# SCH_HallVoltageLV25np.net
KiCad netlist of a schematic drawn in Altium Designer
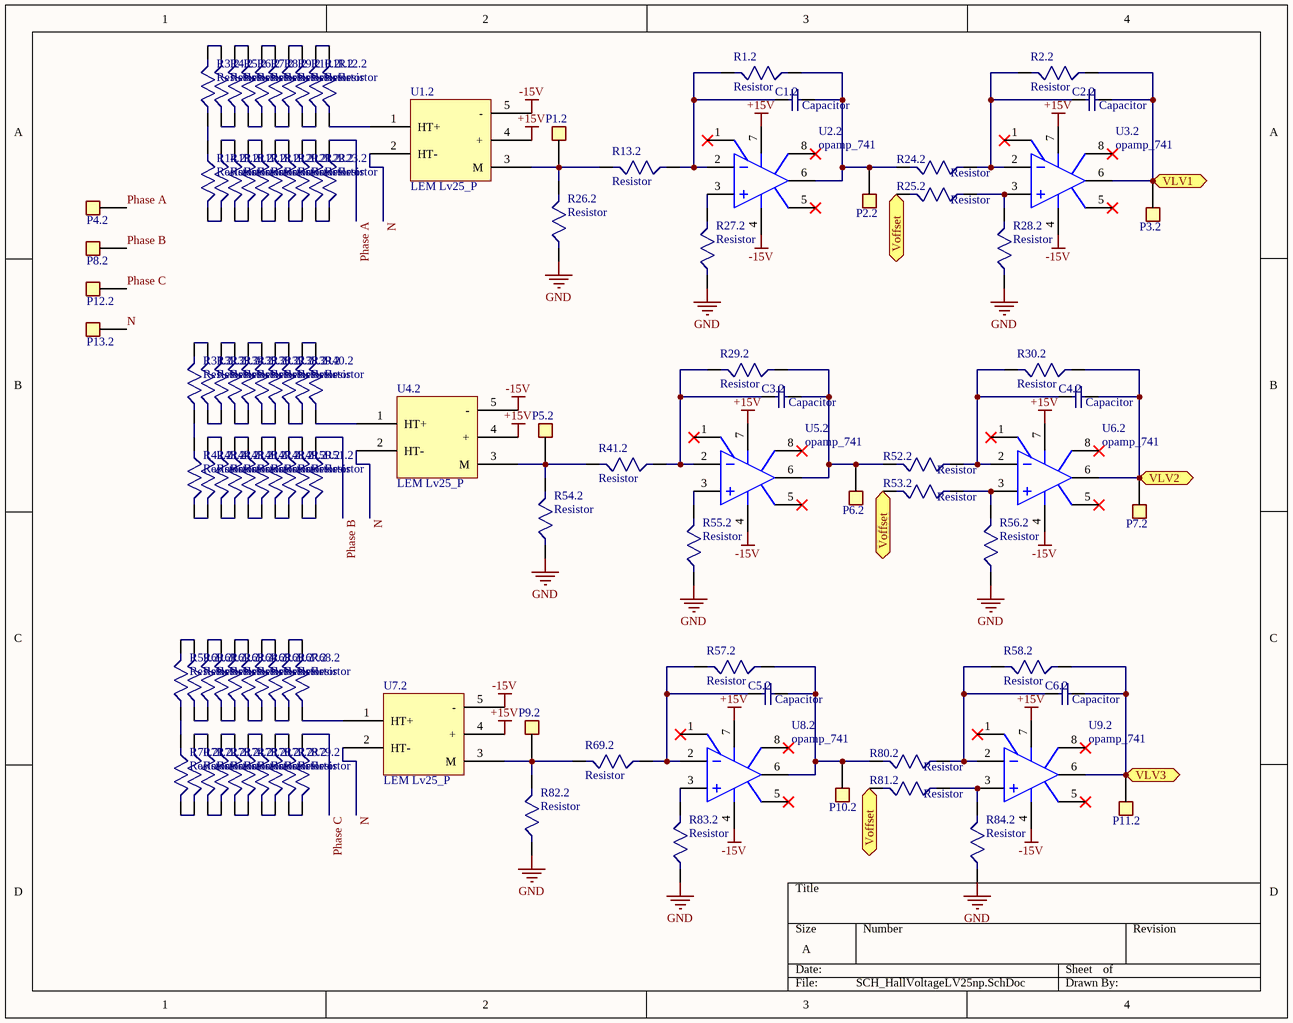
[diagram p0: SCH_HallVoltageLV25np.SchDoc]

(export (version "E")
  (design (tool "Eeschema 10.0.6"))
  (components
    (comp (ref "C1.2")
      (value "Capacitor")
      (footprint "CAPC0805")
      (description "capacitor non polar")
      (libsource (lib "thuvien_altium") (part "capacitor_non_polar"))
    )
    (comp (ref "C2.2")
      (value "Capacitor")
      (footprint "CAPC0805")
      (description "capacitor non polar")
      (libsource (lib "thuvien_altium") (part "capacitor_non_polar"))
    )
    (comp (ref "C3.2")
      (value "Capacitor")
      (footprint "CAPC0805")
      (description "capacitor non polar")
      (libsource (lib "thuvien_altium") (part "capacitor_non_polar"))
    )
    (comp (ref "C4.2")
      (value "Capacitor")
      (footprint "CAPC0805")
      (description "capacitor non polar")
      (libsource (lib "thuvien_altium") (part "capacitor_non_polar"))
    )
    (comp (ref "C5.2")
      (value "Capacitor")
      (footprint "CAPC0805")
      (description "capacitor non polar")
      (libsource (lib "thuvien_altium") (part "capacitor_non_polar"))
    )
    (comp (ref "C6.2")
      (value "Capacitor")
      (footprint "CAPC0805")
      (description "capacitor non polar")
      (libsource (lib "thuvien_altium") (part "capacitor_non_polar"))
    )
    (comp (ref "P1.2")
      (value "testpin")
      (footprint "thuvien_altium:tp_red_1p")
      (libsource (lib "") (part "testpin_1"))
    )
    (comp (ref "P2.2")
      (value "testpin")
      (footprint "thuvien_altium:tp_red_1p")
      (libsource (lib "thuvien_altium") (part "testpin"))
    )
    (comp (ref "P3.2")
      (value "testpin")
      (footprint "thuvien_altium:tp_red_1p")
      (libsource (lib "thuvien_altium") (part "testpin"))
    )
    (comp (ref "P4.2")
      (value "Terminal on PCB")
      (footprint "thuvien_altium:Terminal M5")
      (libsource (lib "thuvien_altium") (part "Terminal on PCB"))
    )
    (comp (ref "P5.2")
      (value "testpin")
      (footprint "thuvien_altium:tp_red_1p")
      (libsource (lib "") (part "testpin_1"))
    )
    (comp (ref "P6.2")
      (value "testpin")
      (footprint "thuvien_altium:tp_red_1p")
      (libsource (lib "thuvien_altium") (part "testpin"))
    )
    (comp (ref "P7.2")
      (value "testpin")
      (footprint "thuvien_altium:tp_red_1p")
      (libsource (lib "thuvien_altium") (part "testpin"))
    )
    (comp (ref "P8.2")
      (value "Terminal on PCB")
      (footprint "thuvien_altium:Terminal M5")
      (libsource (lib "thuvien_altium") (part "Terminal on PCB"))
    )
    (comp (ref "P9.2")
      (value "testpin")
      (footprint "thuvien_altium:tp_red_1p")
      (libsource (lib "") (part "testpin_1"))
    )
    (comp (ref "P10.2")
      (value "testpin")
      (footprint "thuvien_altium:tp_red_1p")
      (libsource (lib "thuvien_altium") (part "testpin"))
    )
    (comp (ref "P11.2")
      (value "testpin")
      (footprint "thuvien_altium:tp_red_1p")
      (libsource (lib "thuvien_altium") (part "testpin"))
    )
    (comp (ref "P12.2")
      (value "Terminal on PCB")
      (footprint "thuvien_altium:Terminal M5")
      (libsource (lib "thuvien_altium") (part "Terminal on PCB"))
    )
    (comp (ref "P13.2")
      (value "Terminal on PCB")
      (footprint "thuvien_altium:Terminal M5")
      (libsource (lib "thuvien_altium") (part "Terminal on PCB"))
    )
    (comp (ref "R1.2")
      (value "Resistor")
      (footprint "RESC0805")
      (description "resistor")
      (libsource (lib "thuvien_altium") (part "resistor"))
    )
    (comp (ref "R2.2")
      (value "Resistor")
      (footprint "RESC0805")
      (description "resistor")
      (libsource (lib "thuvien_altium") (part "resistor"))
    )
    (comp (ref "R3.2")
      (value "Resistor")
      (footprint "RESC0805")
      (description "resistor")
      (libsource (lib "thuvien_altium") (part "resistor"))
    )
    (comp (ref "R4.2")
      (value "Resistor")
      (footprint "RESC0805")
      (description "resistor")
      (libsource (lib "thuvien_altium") (part "resistor"))
    )
    (comp (ref "R5.2")
      (value "Resistor")
      (footprint "RESC0805")
      (description "resistor")
      (libsource (lib "thuvien_altium") (part "resistor"))
    )
    (comp (ref "R6.2")
      (value "Resistor")
      (footprint "RESC0805")
      (description "resistor")
      (libsource (lib "thuvien_altium") (part "resistor"))
    )
    (comp (ref "R7.2")
      (value "Resistor")
      (footprint "RESC0805")
      (description "resistor")
      (libsource (lib "thuvien_altium") (part "resistor"))
    )
    (comp (ref "R8.2")
      (value "Resistor")
      (footprint "RESC0805")
      (description "resistor")
      (libsource (lib "thuvien_altium") (part "resistor"))
    )
    (comp (ref "R9.2")
      (value "Resistor")
      (footprint "RESC0805")
      (description "resistor")
      (libsource (lib "thuvien_altium") (part "resistor"))
    )
    (comp (ref "R10.2")
      (value "Resistor")
      (footprint "RESC0805")
      (description "resistor")
      (libsource (lib "thuvien_altium") (part "resistor"))
    )
    (comp (ref "R11.2")
      (value "Resistor")
      (footprint "RESC0805")
      (description "resistor")
      (libsource (lib "thuvien_altium") (part "resistor"))
    )
    (comp (ref "R12.2")
      (value "Resistor")
      (footprint "RESC0805")
      (description "resistor")
      (libsource (lib "thuvien_altium") (part "resistor"))
    )
    (comp (ref "R13.2")
      (value "Resistor")
      (footprint "RESC0805")
      (description "resistor")
      (libsource (lib "thuvien_altium") (part "resistor"))
    )
    (comp (ref "R14.2")
      (value "Resistor")
      (footprint "RESC0805")
      (description "resistor")
      (libsource (lib "thuvien_altium") (part "resistor"))
    )
    (comp (ref "R15.2")
      (value "Resistor")
      (footprint "RESC0805")
      (description "resistor")
      (libsource (lib "thuvien_altium") (part "resistor"))
    )
    (comp (ref "R16.2")
      (value "Resistor")
      (footprint "RESC0805")
      (description "resistor")
      (libsource (lib "thuvien_altium") (part "resistor"))
    )
    (comp (ref "R17.2")
      (value "Resistor")
      (footprint "RESC0805")
      (description "resistor")
      (libsource (lib "thuvien_altium") (part "resistor"))
    )
    (comp (ref "R18.2")
      (value "Resistor")
      (footprint "RESC0805")
      (description "resistor")
      (libsource (lib "thuvien_altium") (part "resistor"))
    )
    (comp (ref "R19.2")
      (value "Resistor")
      (footprint "RESC0805")
      (description "resistor")
      (libsource (lib "thuvien_altium") (part "resistor"))
    )
    (comp (ref "R20.2")
      (value "Resistor")
      (footprint "RESC0805")
      (description "resistor")
      (libsource (lib "thuvien_altium") (part "resistor"))
    )
    (comp (ref "R21.2")
      (value "Resistor")
      (footprint "RESC0805")
      (description "resistor")
      (libsource (lib "thuvien_altium") (part "resistor"))
    )
    (comp (ref "R22.2")
      (value "Resistor")
      (footprint "RESC0805")
      (description "resistor")
      (libsource (lib "thuvien_altium") (part "resistor"))
    )
    (comp (ref "R23.2")
      (value "Resistor")
      (footprint "RESC0805")
      (description "resistor")
      (libsource (lib "thuvien_altium") (part "resistor"))
    )
    (comp (ref "R24.2")
      (value "Resistor")
      (footprint "RESC0805")
      (description "resistor")
      (libsource (lib "thuvien_altium") (part "resistor"))
    )
    (comp (ref "R25.2")
      (value "Resistor")
      (footprint "RESC0805")
      (description "resistor")
      (libsource (lib "thuvien_altium") (part "resistor"))
    )
    (comp (ref "R26.2")
      (value "Resistor")
      (footprint "RESC0805")
      (description "resistor")
      (libsource (lib "thuvien_altium") (part "resistor"))
    )
    (comp (ref "R27.2")
      (value "Resistor")
      (footprint "RESC0805")
      (description "resistor")
      (libsource (lib "thuvien_altium") (part "resistor"))
    )
    (comp (ref "R28.2")
      (value "Resistor")
      (footprint "RESC0805")
      (description "resistor")
      (libsource (lib "thuvien_altium") (part "resistor"))
    )
    (comp (ref "R29.2")
      (value "Resistor")
      (footprint "RESC0805")
      (description "resistor")
      (libsource (lib "thuvien_altium") (part "resistor"))
    )
    (comp (ref "R30.2")
      (value "Resistor")
      (footprint "RESC0805")
      (description "resistor")
      (libsource (lib "thuvien_altium") (part "resistor"))
    )
    (comp (ref "R31.2")
      (value "Resistor")
      (footprint "RESC0805")
      (description "resistor")
      (libsource (lib "thuvien_altium") (part "resistor"))
    )
    (comp (ref "R32.2")
      (value "Resistor")
      (footprint "RESC0805")
      (description "resistor")
      (libsource (lib "thuvien_altium") (part "resistor"))
    )
    (comp (ref "R33.2")
      (value "Resistor")
      (footprint "RESC0805")
      (description "resistor")
      (libsource (lib "thuvien_altium") (part "resistor"))
    )
    (comp (ref "R34.2")
      (value "Resistor")
      (footprint "RESC0805")
      (description "resistor")
      (libsource (lib "thuvien_altium") (part "resistor"))
    )
    (comp (ref "R35.2")
      (value "Resistor")
      (footprint "RESC0805")
      (description "resistor")
      (libsource (lib "thuvien_altium") (part "resistor"))
    )
    (comp (ref "R36.2")
      (value "Resistor")
      (footprint "RESC0805")
      (description "resistor")
      (libsource (lib "thuvien_altium") (part "resistor"))
    )
    (comp (ref "R37.2")
      (value "Resistor")
      (footprint "RESC0805")
      (description "resistor")
      (libsource (lib "thuvien_altium") (part "resistor"))
    )
    (comp (ref "R38.2")
      (value "Resistor")
      (footprint "RESC0805")
      (description "resistor")
      (libsource (lib "thuvien_altium") (part "resistor"))
    )
    (comp (ref "R39.2")
      (value "Resistor")
      (footprint "RESC0805")
      (description "resistor")
      (libsource (lib "thuvien_altium") (part "resistor"))
    )
    (comp (ref "R40.2")
      (value "Resistor")
      (footprint "RESC0805")
      (description "resistor")
      (libsource (lib "thuvien_altium") (part "resistor"))
    )
    (comp (ref "R41.2")
      (value "Resistor")
      (footprint "RESC0805")
      (description "resistor")
      (libsource (lib "thuvien_altium") (part "resistor"))
    )
    (comp (ref "R42.2")
      (value "Resistor")
      (footprint "RESC0805")
      (description "resistor")
      (libsource (lib "thuvien_altium") (part "resistor"))
    )
    (comp (ref "R43.2")
      (value "Resistor")
      (footprint "RESC0805")
      (description "resistor")
      (libsource (lib "thuvien_altium") (part "resistor"))
    )
    (comp (ref "R44.2")
      (value "Resistor")
      (footprint "RESC0805")
      (description "resistor")
      (libsource (lib "thuvien_altium") (part "resistor"))
    )
    (comp (ref "R45.2")
      (value "Resistor")
      (footprint "RESC0805")
      (description "resistor")
      (libsource (lib "thuvien_altium") (part "resistor"))
    )
    (comp (ref "R46.2")
      (value "Resistor")
      (footprint "RESC0805")
      (description "resistor")
      (libsource (lib "thuvien_altium") (part "resistor"))
    )
    (comp (ref "R47.2")
      (value "Resistor")
      (footprint "RESC0805")
      (description "resistor")
      (libsource (lib "thuvien_altium") (part "resistor"))
    )
    (comp (ref "R48.2")
      (value "Resistor")
      (footprint "RESC0805")
      (description "resistor")
      (libsource (lib "thuvien_altium") (part "resistor"))
    )
    (comp (ref "R49.2")
      (value "Resistor")
      (footprint "RESC0805")
      (description "resistor")
      (libsource (lib "thuvien_altium") (part "resistor"))
    )
    (comp (ref "R50.2")
      (value "Resistor")
      (footprint "RESC0805")
      (description "resistor")
      (libsource (lib "thuvien_altium") (part "resistor"))
    )
    (comp (ref "R51.2")
      (value "Resistor")
      (footprint "RESC0805")
      (description "resistor")
      (libsource (lib "thuvien_altium") (part "resistor"))
    )
    (comp (ref "R52.2")
      (value "Resistor")
      (footprint "RESC0805")
      (description "resistor")
      (libsource (lib "thuvien_altium") (part "resistor"))
    )
    (comp (ref "R53.2")
      (value "Resistor")
      (footprint "RESC0805")
      (description "resistor")
      (libsource (lib "thuvien_altium") (part "resistor"))
    )
    (comp (ref "R54.2")
      (value "Resistor")
      (footprint "RESC0805")
      (description "resistor")
      (libsource (lib "thuvien_altium") (part "resistor"))
    )
    (comp (ref "R55.2")
      (value "Resistor")
      (footprint "RESC0805")
      (description "resistor")
      (libsource (lib "thuvien_altium") (part "resistor"))
    )
    (comp (ref "R56.2")
      (value "Resistor")
      (footprint "RESC0805")
      (description "resistor")
      (libsource (lib "thuvien_altium") (part "resistor"))
    )
    (comp (ref "R57.2")
      (value "Resistor")
      (footprint "RESC0805")
      (description "resistor")
      (libsource (lib "thuvien_altium") (part "resistor"))
    )
    (comp (ref "R58.2")
      (value "Resistor")
      (footprint "RESC0805")
      (description "resistor")
      (libsource (lib "thuvien_altium") (part "resistor"))
    )
    (comp (ref "R59.2")
      (value "Resistor")
      (footprint "RESC0805")
      (description "resistor")
      (libsource (lib "thuvien_altium") (part "resistor"))
    )
    (comp (ref "R60.2")
      (value "Resistor")
      (footprint "RESC0805")
      (description "resistor")
      (libsource (lib "thuvien_altium") (part "resistor"))
    )
    (comp (ref "R61.2")
      (value "Resistor")
      (footprint "RESC0805")
      (description "resistor")
      (libsource (lib "thuvien_altium") (part "resistor"))
    )
    (comp (ref "R62.2")
      (value "Resistor")
      (footprint "RESC0805")
      (description "resistor")
      (libsource (lib "thuvien_altium") (part "resistor"))
    )
    (comp (ref "R63.2")
      (value "Resistor")
      (footprint "RESC0805")
      (description "resistor")
      (libsource (lib "thuvien_altium") (part "resistor"))
    )
    (comp (ref "R64.2")
      (value "Resistor")
      (footprint "RESC0805")
      (description "resistor")
      (libsource (lib "thuvien_altium") (part "resistor"))
    )
    (comp (ref "R65.2")
      (value "Resistor")
      (footprint "RESC0805")
      (description "resistor")
      (libsource (lib "thuvien_altium") (part "resistor"))
    )
    (comp (ref "R66.2")
      (value "Resistor")
      (footprint "RESC0805")
      (description "resistor")
      (libsource (lib "thuvien_altium") (part "resistor"))
    )
    (comp (ref "R67.2")
      (value "Resistor")
      (footprint "RESC0805")
      (description "resistor")
      (libsource (lib "thuvien_altium") (part "resistor"))
    )
    (comp (ref "R68.2")
      (value "Resistor")
      (footprint "RESC0805")
      (description "resistor")
      (libsource (lib "thuvien_altium") (part "resistor"))
    )
    (comp (ref "R69.2")
      (value "Resistor")
      (footprint "RESC0805")
      (description "resistor")
      (libsource (lib "thuvien_altium") (part "resistor"))
    )
    (comp (ref "R70.2")
      (value "Resistor")
      (footprint "RESC0805")
      (description "resistor")
      (libsource (lib "thuvien_altium") (part "resistor"))
    )
    (comp (ref "R71.2")
      (value "Resistor")
      (footprint "RESC0805")
      (description "resistor")
      (libsource (lib "thuvien_altium") (part "resistor"))
    )
    (comp (ref "R72.2")
      (value "Resistor")
      (footprint "RESC0805")
      (description "resistor")
      (libsource (lib "thuvien_altium") (part "resistor"))
    )
    (comp (ref "R73.2")
      (value "Resistor")
      (footprint "RESC0805")
      (description "resistor")
      (libsource (lib "thuvien_altium") (part "resistor"))
    )
    (comp (ref "R74.2")
      (value "Resistor")
      (footprint "RESC0805")
      (description "resistor")
      (libsource (lib "thuvien_altium") (part "resistor"))
    )
    (comp (ref "R75.2")
      (value "Resistor")
      (footprint "RESC0805")
      (description "resistor")
      (libsource (lib "thuvien_altium") (part "resistor"))
    )
    (comp (ref "R76.2")
      (value "Resistor")
      (footprint "RESC0805")
      (description "resistor")
      (libsource (lib "thuvien_altium") (part "resistor"))
    )
    (comp (ref "R77.2")
      (value "Resistor")
      (footprint "RESC0805")
      (description "resistor")
      (libsource (lib "thuvien_altium") (part "resistor"))
    )
    (comp (ref "R78.2")
      (value "Resistor")
      (footprint "RESC0805")
      (description "resistor")
      (libsource (lib "thuvien_altium") (part "resistor"))
    )
    (comp (ref "R79.2")
      (value "Resistor")
      (footprint "RESC0805")
      (description "resistor")
      (libsource (lib "thuvien_altium") (part "resistor"))
    )
    (comp (ref "R80.2")
      (value "Resistor")
      (footprint "RESC0805")
      (description "resistor")
      (libsource (lib "thuvien_altium") (part "resistor"))
    )
    (comp (ref "R81.2")
      (value "Resistor")
      (footprint "RESC0805")
      (description "resistor")
      (libsource (lib "thuvien_altium") (part "resistor"))
    )
    (comp (ref "R82.2")
      (value "Resistor")
      (footprint "RESC0805")
      (description "resistor")
      (libsource (lib "thuvien_altium") (part "resistor"))
    )
    (comp (ref "R83.2")
      (value "Resistor")
      (footprint "RESC0805")
      (description "resistor")
      (libsource (lib "thuvien_altium") (part "resistor"))
    )
    (comp (ref "R84.2")
      (value "Resistor")
      (footprint "RESC0805")
      (description "resistor")
      (libsource (lib "thuvien_altium") (part "resistor"))
    )
    (comp (ref "U1.2")
      (value "LEM Lv25_P")
      (footprint "thuvien_altium:LEN LV25_P")
      (libsource (lib "thuvien_altium") (part "LEM LV25_P"))
    )
    (comp (ref "U2.2")
      (value "opamp_741")
      (footprint "thuvien_altium:SOIC-8_dan")
      (libsource (lib "thuvien_altium") (part "opamp 741"))
    )
    (comp (ref "U3.2")
      (value "opamp_741")
      (footprint "thuvien_altium:SOIC-8_dan")
      (libsource (lib "thuvien_altium") (part "opamp 741"))
    )
    (comp (ref "U4.2")
      (value "LEM Lv25_P")
      (footprint "thuvien_altium:LEN LV25_P")
      (libsource (lib "thuvien_altium") (part "LEM LV25_P"))
    )
    (comp (ref "U5.2")
      (value "opamp_741")
      (footprint "thuvien_altium:SOIC-8_dan")
      (libsource (lib "thuvien_altium") (part "opamp 741"))
    )
    (comp (ref "U6.2")
      (value "opamp_741")
      (footprint "thuvien_altium:SOIC-8_dan")
      (libsource (lib "thuvien_altium") (part "opamp 741"))
    )
    (comp (ref "U7.2")
      (value "LEM Lv25_P")
      (footprint "thuvien_altium:LEN LV25_P")
      (libsource (lib "thuvien_altium") (part "LEM LV25_P"))
    )
    (comp (ref "U8.2")
      (value "opamp_741")
      (footprint "thuvien_altium:SOIC-8_dan")
      (libsource (lib "thuvien_altium") (part "opamp 741"))
    )
    (comp (ref "U9.2")
      (value "opamp_741")
      (footprint "thuvien_altium:SOIC-8_dan")
      (libsource (lib "thuvien_altium") (part "opamp 741"))
    )
  )
  (nets
    (net (code "1") (name "+15V") (class "Default")
      (node (ref "U1.2") (pin "4") (pinfunction "+_4") (pintype "passive"))
      (node (ref "U2.2") (pin "7") (pinfunction "V+_7") (pintype "power_in"))
      (node (ref "U3.2") (pin "7") (pinfunction "V+_7") (pintype "power_in"))
      (node (ref "U4.2") (pin "4") (pinfunction "+_4") (pintype "passive"))
      (node (ref "U5.2") (pin "7") (pinfunction "V+_7") (pintype "power_in"))
      (node (ref "U6.2") (pin "7") (pinfunction "V+_7") (pintype "power_in"))
      (node (ref "U7.2") (pin "4") (pinfunction "+_4") (pintype "passive"))
      (node (ref "U8.2") (pin "7") (pinfunction "V+_7") (pintype "power_in"))
      (node (ref "U9.2") (pin "7") (pinfunction "V+_7") (pintype "power_in"))
    )
    (net (code "2") (name "-15V") (class "Default")
      (node (ref "U1.2") (pin "5") (pinfunction "-_5") (pintype "passive"))
      (node (ref "U2.2") (pin "4") (pinfunction "V-_4") (pintype "power_in"))
      (node (ref "U3.2") (pin "4") (pinfunction "V-_4") (pintype "power_in"))
      (node (ref "U4.2") (pin "5") (pinfunction "-_5") (pintype "passive"))
      (node (ref "U5.2") (pin "4") (pinfunction "V-_4") (pintype "power_in"))
      (node (ref "U6.2") (pin "4") (pinfunction "V-_4") (pintype "power_in"))
      (node (ref "U7.2") (pin "5") (pinfunction "-_5") (pintype "passive"))
      (node (ref "U8.2") (pin "4") (pinfunction "V-_4") (pintype "power_in"))
      (node (ref "U9.2") (pin "4") (pinfunction "V-_4") (pintype "power_in"))
    )
    (net (code "3") (name "/N") (class "Default")
      (node (ref "P13.2") (pin "1") (pinfunction "1_1") (pintype "power_in"))
      (node (ref "U1.2") (pin "2") (pinfunction "HT-_2") (pintype "passive"))
      (node (ref "U4.2") (pin "2") (pinfunction "HT-_2") (pintype "passive"))
      (node (ref "U7.2") (pin "2") (pinfunction "HT-_2") (pintype "passive"))
    )
    (net (code "4") (name "/Phase A") (class "Default")
      (node (ref "P4.2") (pin "1") (pinfunction "1_1") (pintype "power_in"))
      (node (ref "R23.2") (pin "1") (pinfunction "1_1") (pintype "power_in"))
    )
    (net (code "5") (name "/Phase B") (class "Default")
      (node (ref "P8.2") (pin "1") (pinfunction "1_1") (pintype "power_in"))
      (node (ref "R51.2") (pin "1") (pinfunction "1_1") (pintype "power_in"))
    )
    (net (code "6") (name "/Phase C") (class "Default")
      (node (ref "P12.2") (pin "1") (pinfunction "1_1") (pintype "power_in"))
      (node (ref "R79.2") (pin "1") (pinfunction "1_1") (pintype "power_in"))
    )
    (net (code "7") (name "/VLV1") (class "Default")
      (node (ref "C2.2") (pin "2") (pinfunction "2_2") (pintype "power_in"))
      (node (ref "P3.2") (pin "1") (pinfunction "1_1") (pintype "power_in"))
      (node (ref "R2.2") (pin "1") (pinfunction "1_1") (pintype "power_in"))
      (node (ref "U3.2") (pin "6") (pinfunction "OUT_6") (pintype "power_in"))
    )
    (net (code "8") (name "/VLV2") (class "Default")
      (node (ref "C4.2") (pin "2") (pinfunction "2_2") (pintype "power_in"))
      (node (ref "P7.2") (pin "1") (pinfunction "1_1") (pintype "power_in"))
      (node (ref "R30.2") (pin "1") (pinfunction "1_1") (pintype "power_in"))
      (node (ref "U6.2") (pin "6") (pinfunction "OUT_6") (pintype "power_in"))
    )
    (net (code "9") (name "/VLV3") (class "Default")
      (node (ref "C6.2") (pin "2") (pinfunction "2_2") (pintype "power_in"))
      (node (ref "P11.2") (pin "1") (pinfunction "1_1") (pintype "power_in"))
      (node (ref "R58.2") (pin "1") (pinfunction "1_1") (pintype "power_in"))
      (node (ref "U9.2") (pin "6") (pinfunction "OUT_6") (pintype "power_in"))
    )
    (net (code "10") (name "/Voffset") (class "Default")
      (node (ref "R25.2") (pin "2") (pinfunction "2_2") (pintype "power_in"))
      (node (ref "R53.2") (pin "2") (pinfunction "2_2") (pintype "power_in"))
      (node (ref "R81.2") (pin "2") (pinfunction "2_2") (pintype "power_in"))
    )
    (net (code "11") (name "GND") (class "Default")
      (node (ref "R26.2") (pin "1") (pinfunction "1_1") (pintype "power_in"))
      (node (ref "R27.2") (pin "1") (pinfunction "1_1") (pintype "power_in"))
      (node (ref "R28.2") (pin "1") (pinfunction "1_1") (pintype "power_in"))
      (node (ref "R54.2") (pin "1") (pinfunction "1_1") (pintype "power_in"))
      (node (ref "R55.2") (pin "1") (pinfunction "1_1") (pintype "power_in"))
      (node (ref "R56.2") (pin "1") (pinfunction "1_1") (pintype "power_in"))
      (node (ref "R82.2") (pin "1") (pinfunction "1_1") (pintype "power_in"))
      (node (ref "R83.2") (pin "1") (pinfunction "1_1") (pintype "power_in"))
      (node (ref "R84.2") (pin "1") (pinfunction "1_1") (pintype "power_in"))
    )
    (net (code "12") (name "Net-(R3.2-Pad2)") (class "Default")
      (node (ref "R3.2") (pin "2") (pinfunction "2_2") (pintype "power_in"))
      (node (ref "R4.2") (pin "2") (pinfunction "2_2") (pintype "power_in"))
    )
    (net (code "13") (name "Net-(R4.2-Pad1)") (class "Default")
      (node (ref "R4.2") (pin "1") (pinfunction "1_1") (pintype "power_in"))
      (node (ref "R5.2") (pin "1") (pinfunction "1_1") (pintype "power_in"))
    )
    (net (code "14") (name "Net-(R5.2-Pad2)") (class "Default")
      (node (ref "R5.2") (pin "2") (pinfunction "2_2") (pintype "power_in"))
      (node (ref "R6.2") (pin "2") (pinfunction "2_2") (pintype "power_in"))
    )
    (net (code "15") (name "Net-(R6.2-Pad1)") (class "Default")
      (node (ref "R6.2") (pin "1") (pinfunction "1_1") (pintype "power_in"))
      (node (ref "R7.2") (pin "1") (pinfunction "1_1") (pintype "power_in"))
    )
    (net (code "16") (name "Net-(R7.2-Pad2)") (class "Default")
      (node (ref "R7.2") (pin "2") (pinfunction "2_2") (pintype "power_in"))
      (node (ref "R8.2") (pin "2") (pinfunction "2_2") (pintype "power_in"))
    )
    (net (code "17") (name "Net-(R8.2-Pad1)") (class "Default")
      (node (ref "R8.2") (pin "1") (pinfunction "1_1") (pintype "power_in"))
      (node (ref "R9.2") (pin "1") (pinfunction "1_1") (pintype "power_in"))
    )
    (net (code "18") (name "Net-(R10.2-Pad1)") (class "Default")
      (node (ref "R10.2") (pin "1") (pinfunction "1_1") (pintype "power_in"))
      (node (ref "R11.2") (pin "1") (pinfunction "1_1") (pintype "power_in"))
    )
    (net (code "19") (name "Net-(R10.2-Pad2)") (class "Default")
      (node (ref "R10.2") (pin "2") (pinfunction "2_2") (pintype "power_in"))
      (node (ref "R9.2") (pin "2") (pinfunction "2_2") (pintype "power_in"))
    )
    (net (code "20") (name "Net-(R11.2-Pad2)") (class "Default")
      (node (ref "R11.2") (pin "2") (pinfunction "2_2") (pintype "power_in"))
      (node (ref "R12.2") (pin "2") (pinfunction "2_2") (pintype "power_in"))
    )
    (net (code "21") (name "Net-(R14.2-Pad1)") (class "Default")
      (node (ref "R14.2") (pin "1") (pinfunction "1_1") (pintype "power_in"))
      (node (ref "R3.2") (pin "1") (pinfunction "1_1") (pintype "power_in"))
    )
    (net (code "22") (name "Net-(R14.2-Pad2)") (class "Default")
      (node (ref "R14.2") (pin "2") (pinfunction "2_2") (pintype "power_in"))
      (node (ref "R15.2") (pin "2") (pinfunction "2_2") (pintype "power_in"))
    )
    (net (code "23") (name "Net-(R15.2-Pad1)") (class "Default")
      (node (ref "R15.2") (pin "1") (pinfunction "1_1") (pintype "power_in"))
      (node (ref "R16.2") (pin "1") (pinfunction "1_1") (pintype "power_in"))
    )
    (net (code "24") (name "Net-(R16.2-Pad2)") (class "Default")
      (node (ref "R16.2") (pin "2") (pinfunction "2_2") (pintype "power_in"))
      (node (ref "R17.2") (pin "2") (pinfunction "2_2") (pintype "power_in"))
    )
    (net (code "25") (name "Net-(R17.2-Pad1)") (class "Default")
      (node (ref "R17.2") (pin "1") (pinfunction "1_1") (pintype "power_in"))
      (node (ref "R18.2") (pin "1") (pinfunction "1_1") (pintype "power_in"))
    )
    (net (code "26") (name "Net-(R18.2-Pad2)") (class "Default")
      (node (ref "R18.2") (pin "2") (pinfunction "2_2") (pintype "power_in"))
      (node (ref "R19.2") (pin "2") (pinfunction "2_2") (pintype "power_in"))
    )
    (net (code "27") (name "Net-(R19.2-Pad1)") (class "Default")
      (node (ref "R19.2") (pin "1") (pinfunction "1_1") (pintype "power_in"))
      (node (ref "R20.2") (pin "1") (pinfunction "1_1") (pintype "power_in"))
    )
    (net (code "28") (name "Net-(R20.2-Pad2)") (class "Default")
      (node (ref "R20.2") (pin "2") (pinfunction "2_2") (pintype "power_in"))
      (node (ref "R21.2") (pin "2") (pinfunction "2_2") (pintype "power_in"))
    )
    (net (code "29") (name "Net-(R21.2-Pad1)") (class "Default")
      (node (ref "R21.2") (pin "1") (pinfunction "1_1") (pintype "power_in"))
      (node (ref "R22.2") (pin "1") (pinfunction "1_1") (pintype "power_in"))
    )
    (net (code "30") (name "Net-(R22.2-Pad2)") (class "Default")
      (node (ref "R22.2") (pin "2") (pinfunction "2_2") (pintype "power_in"))
      (node (ref "R23.2") (pin "2") (pinfunction "2_2") (pintype "power_in"))
    )
    (net (code "31") (name "Net-(R31.2-Pad1)") (class "Default")
      (node (ref "R31.2") (pin "1") (pinfunction "1_1") (pintype "power_in"))
      (node (ref "R42.2") (pin "1") (pinfunction "1_1") (pintype "power_in"))
    )
    (net (code "32") (name "Net-(R31.2-Pad2)") (class "Default")
      (node (ref "R31.2") (pin "2") (pinfunction "2_2") (pintype "power_in"))
      (node (ref "R32.2") (pin "2") (pinfunction "2_2") (pintype "power_in"))
    )
    (net (code "33") (name "Net-(R32.2-Pad1)") (class "Default")
      (node (ref "R32.2") (pin "1") (pinfunction "1_1") (pintype "power_in"))
      (node (ref "R33.2") (pin "1") (pinfunction "1_1") (pintype "power_in"))
    )
    (net (code "34") (name "Net-(R33.2-Pad2)") (class "Default")
      (node (ref "R33.2") (pin "2") (pinfunction "2_2") (pintype "power_in"))
      (node (ref "R34.2") (pin "2") (pinfunction "2_2") (pintype "power_in"))
    )
    (net (code "35") (name "Net-(R34.2-Pad1)") (class "Default")
      (node (ref "R34.2") (pin "1") (pinfunction "1_1") (pintype "power_in"))
      (node (ref "R35.2") (pin "1") (pinfunction "1_1") (pintype "power_in"))
    )
    (net (code "36") (name "Net-(R35.2-Pad2)") (class "Default")
      (node (ref "R35.2") (pin "2") (pinfunction "2_2") (pintype "power_in"))
      (node (ref "R36.2") (pin "2") (pinfunction "2_2") (pintype "power_in"))
    )
    (net (code "37") (name "Net-(R36.2-Pad1)") (class "Default")
      (node (ref "R36.2") (pin "1") (pinfunction "1_1") (pintype "power_in"))
      (node (ref "R37.2") (pin "1") (pinfunction "1_1") (pintype "power_in"))
    )
    (net (code "38") (name "Net-(R37.2-Pad2)") (class "Default")
      (node (ref "R37.2") (pin "2") (pinfunction "2_2") (pintype "power_in"))
      (node (ref "R38.2") (pin "2") (pinfunction "2_2") (pintype "power_in"))
    )
    (net (code "39") (name "Net-(R38.2-Pad1)") (class "Default")
      (node (ref "R38.2") (pin "1") (pinfunction "1_1") (pintype "power_in"))
      (node (ref "R39.2") (pin "1") (pinfunction "1_1") (pintype "power_in"))
    )
    (net (code "40") (name "Net-(R39.2-Pad2)") (class "Default")
      (node (ref "R39.2") (pin "2") (pinfunction "2_2") (pintype "power_in"))
      (node (ref "R40.2") (pin "2") (pinfunction "2_2") (pintype "power_in"))
    )
    (net (code "41") (name "Net-(R42.2-Pad2)") (class "Default")
      (node (ref "R42.2") (pin "2") (pinfunction "2_2") (pintype "power_in"))
      (node (ref "R43.2") (pin "2") (pinfunction "2_2") (pintype "power_in"))
    )
    (net (code "42") (name "Net-(R43.2-Pad1)") (class "Default")
      (node (ref "R43.2") (pin "1") (pinfunction "1_1") (pintype "power_in"))
      (node (ref "R44.2") (pin "1") (pinfunction "1_1") (pintype "power_in"))
    )
    (net (code "43") (name "Net-(R44.2-Pad2)") (class "Default")
      (node (ref "R44.2") (pin "2") (pinfunction "2_2") (pintype "power_in"))
      (node (ref "R45.2") (pin "2") (pinfunction "2_2") (pintype "power_in"))
    )
    (net (code "44") (name "Net-(R45.2-Pad1)") (class "Default")
      (node (ref "R45.2") (pin "1") (pinfunction "1_1") (pintype "power_in"))
      (node (ref "R46.2") (pin "1") (pinfunction "1_1") (pintype "power_in"))
    )
    (net (code "45") (name "Net-(R46.2-Pad2)") (class "Default")
      (node (ref "R46.2") (pin "2") (pinfunction "2_2") (pintype "power_in"))
      (node (ref "R47.2") (pin "2") (pinfunction "2_2") (pintype "power_in"))
    )
    (net (code "46") (name "Net-(R47.2-Pad1)") (class "Default")
      (node (ref "R47.2") (pin "1") (pinfunction "1_1") (pintype "power_in"))
      (node (ref "R48.2") (pin "1") (pinfunction "1_1") (pintype "power_in"))
    )
    (net (code "47") (name "Net-(R48.2-Pad2)") (class "Default")
      (node (ref "R48.2") (pin "2") (pinfunction "2_2") (pintype "power_in"))
      (node (ref "R49.2") (pin "2") (pinfunction "2_2") (pintype "power_in"))
    )
    (net (code "48") (name "Net-(R49.2-Pad1)") (class "Default")
      (node (ref "R49.2") (pin "1") (pinfunction "1_1") (pintype "power_in"))
      (node (ref "R50.2") (pin "1") (pinfunction "1_1") (pintype "power_in"))
    )
    (net (code "49") (name "Net-(R50.2-Pad2)") (class "Default")
      (node (ref "R50.2") (pin "2") (pinfunction "2_2") (pintype "power_in"))
      (node (ref "R51.2") (pin "2") (pinfunction "2_2") (pintype "power_in"))
    )
    (net (code "50") (name "Net-(R59.2-Pad1)") (class "Default")
      (node (ref "R59.2") (pin "1") (pinfunction "1_1") (pintype "power_in"))
      (node (ref "R70.2") (pin "1") (pinfunction "1_1") (pintype "power_in"))
    )
    (net (code "51") (name "Net-(R59.2-Pad2)") (class "Default")
      (node (ref "R59.2") (pin "2") (pinfunction "2_2") (pintype "power_in"))
      (node (ref "R60.2") (pin "2") (pinfunction "2_2") (pintype "power_in"))
    )
    (net (code "52") (name "Net-(R60.2-Pad1)") (class "Default")
      (node (ref "R60.2") (pin "1") (pinfunction "1_1") (pintype "power_in"))
      (node (ref "R61.2") (pin "1") (pinfunction "1_1") (pintype "power_in"))
    )
    (net (code "53") (name "Net-(R61.2-Pad2)") (class "Default")
      (node (ref "R61.2") (pin "2") (pinfunction "2_2") (pintype "power_in"))
      (node (ref "R62.2") (pin "2") (pinfunction "2_2") (pintype "power_in"))
    )
    (net (code "54") (name "Net-(R62.2-Pad1)") (class "Default")
      (node (ref "R62.2") (pin "1") (pinfunction "1_1") (pintype "power_in"))
      (node (ref "R63.2") (pin "1") (pinfunction "1_1") (pintype "power_in"))
    )
    (net (code "55") (name "Net-(R63.2-Pad2)") (class "Default")
      (node (ref "R63.2") (pin "2") (pinfunction "2_2") (pintype "power_in"))
      (node (ref "R64.2") (pin "2") (pinfunction "2_2") (pintype "power_in"))
    )
    (net (code "56") (name "Net-(R64.2-Pad1)") (class "Default")
      (node (ref "R64.2") (pin "1") (pinfunction "1_1") (pintype "power_in"))
      (node (ref "R65.2") (pin "1") (pinfunction "1_1") (pintype "power_in"))
    )
    (net (code "57") (name "Net-(R65.2-Pad2)") (class "Default")
      (node (ref "R65.2") (pin "2") (pinfunction "2_2") (pintype "power_in"))
      (node (ref "R66.2") (pin "2") (pinfunction "2_2") (pintype "power_in"))
    )
    (net (code "58") (name "Net-(R66.2-Pad1)") (class "Default")
      (node (ref "R66.2") (pin "1") (pinfunction "1_1") (pintype "power_in"))
      (node (ref "R67.2") (pin "1") (pinfunction "1_1") (pintype "power_in"))
    )
    (net (code "59") (name "Net-(R67.2-Pad2)") (class "Default")
      (node (ref "R67.2") (pin "2") (pinfunction "2_2") (pintype "power_in"))
      (node (ref "R68.2") (pin "2") (pinfunction "2_2") (pintype "power_in"))
    )
    (net (code "60") (name "Net-(R70.2-Pad2)") (class "Default")
      (node (ref "R70.2") (pin "2") (pinfunction "2_2") (pintype "power_in"))
      (node (ref "R71.2") (pin "2") (pinfunction "2_2") (pintype "power_in"))
    )
    (net (code "61") (name "Net-(R71.2-Pad1)") (class "Default")
      (node (ref "R71.2") (pin "1") (pinfunction "1_1") (pintype "power_in"))
      (node (ref "R72.2") (pin "1") (pinfunction "1_1") (pintype "power_in"))
    )
    (net (code "62") (name "Net-(R72.2-Pad2)") (class "Default")
      (node (ref "R72.2") (pin "2") (pinfunction "2_2") (pintype "power_in"))
      (node (ref "R73.2") (pin "2") (pinfunction "2_2") (pintype "power_in"))
    )
    (net (code "63") (name "Net-(R73.2-Pad1)") (class "Default")
      (node (ref "R73.2") (pin "1") (pinfunction "1_1") (pintype "power_in"))
      (node (ref "R74.2") (pin "1") (pinfunction "1_1") (pintype "power_in"))
    )
    (net (code "64") (name "Net-(R74.2-Pad2)") (class "Default")
      (node (ref "R74.2") (pin "2") (pinfunction "2_2") (pintype "power_in"))
      (node (ref "R75.2") (pin "2") (pinfunction "2_2") (pintype "power_in"))
    )
    (net (code "65") (name "Net-(R75.2-Pad1)") (class "Default")
      (node (ref "R75.2") (pin "1") (pinfunction "1_1") (pintype "power_in"))
      (node (ref "R76.2") (pin "1") (pinfunction "1_1") (pintype "power_in"))
    )
    (net (code "66") (name "Net-(R76.2-Pad2)") (class "Default")
      (node (ref "R76.2") (pin "2") (pinfunction "2_2") (pintype "power_in"))
      (node (ref "R77.2") (pin "2") (pinfunction "2_2") (pintype "power_in"))
    )
    (net (code "67") (name "Net-(R77.2-Pad1)") (class "Default")
      (node (ref "R77.2") (pin "1") (pinfunction "1_1") (pintype "power_in"))
      (node (ref "R78.2") (pin "1") (pinfunction "1_1") (pintype "power_in"))
    )
    (net (code "68") (name "Net-(R78.2-Pad2)") (class "Default")
      (node (ref "R78.2") (pin "2") (pinfunction "2_2") (pintype "power_in"))
      (node (ref "R79.2") (pin "2") (pinfunction "2_2") (pintype "power_in"))
    )
    (net (code "69") (name "Net-(U1.2-HT+)") (class "Default")
      (node (ref "R12.2") (pin "1") (pinfunction "1_1") (pintype "power_in"))
      (node (ref "U1.2") (pin "1") (pinfunction "HT+_1") (pintype "passive"))
    )
    (net (code "70") (name "Net-(U1.2-M)") (class "Default")
      (node (ref "P1.2") (pin "1") (pinfunction "1_1") (pintype "power_in"))
      (node (ref "R13.2") (pin "2") (pinfunction "2_2") (pintype "power_in"))
      (node (ref "R26.2") (pin "2") (pinfunction "2_2") (pintype "power_in"))
      (node (ref "U1.2") (pin "3") (pinfunction "M_3") (pintype "passive"))
    )
    (net (code "71") (name "Net-(U2.2-IN+)") (class "Default")
      (node (ref "R27.2") (pin "2") (pinfunction "2_2") (pintype "power_in"))
      (node (ref "U2.2") (pin "3") (pinfunction "IN+_3") (pintype "power_in"))
    )
    (net (code "72") (name "Net-(U2.2-IN-)") (class "Default")
      (node (ref "C1.2") (pin "1") (pinfunction "1_1") (pintype "power_in"))
      (node (ref "R1.2") (pin "2") (pinfunction "2_2") (pintype "power_in"))
      (node (ref "R13.2") (pin "1") (pinfunction "1_1") (pintype "power_in"))
      (node (ref "U2.2") (pin "2") (pinfunction "IN-_2") (pintype "power_in"))
    )
    (net (code "73") (name "Net-(U2.2-OUT)") (class "Default")
      (node (ref "C1.2") (pin "2") (pinfunction "2_2") (pintype "power_in"))
      (node (ref "P2.2") (pin "1") (pinfunction "1_1") (pintype "power_in"))
      (node (ref "R1.2") (pin "1") (pinfunction "1_1") (pintype "power_in"))
      (node (ref "R24.2") (pin "2") (pinfunction "2_2") (pintype "power_in"))
      (node (ref "U2.2") (pin "6") (pinfunction "OUT_6") (pintype "power_in"))
    )
    (net (code "74") (name "Net-(U3.2-IN+)") (class "Default")
      (node (ref "R25.2") (pin "1") (pinfunction "1_1") (pintype "power_in"))
      (node (ref "R28.2") (pin "2") (pinfunction "2_2") (pintype "power_in"))
      (node (ref "U3.2") (pin "3") (pinfunction "IN+_3") (pintype "power_in"))
    )
    (net (code "75") (name "Net-(U3.2-IN-)") (class "Default")
      (node (ref "C2.2") (pin "1") (pinfunction "1_1") (pintype "power_in"))
      (node (ref "R2.2") (pin "2") (pinfunction "2_2") (pintype "power_in"))
      (node (ref "R24.2") (pin "1") (pinfunction "1_1") (pintype "power_in"))
      (node (ref "U3.2") (pin "2") (pinfunction "IN-_2") (pintype "power_in"))
    )
    (net (code "76") (name "Net-(U4.2-HT+)") (class "Default")
      (node (ref "R40.2") (pin "1") (pinfunction "1_1") (pintype "power_in"))
      (node (ref "U4.2") (pin "1") (pinfunction "HT+_1") (pintype "passive"))
    )
    (net (code "77") (name "Net-(U4.2-M)") (class "Default")
      (node (ref "P5.2") (pin "1") (pinfunction "1_1") (pintype "power_in"))
      (node (ref "R41.2") (pin "2") (pinfunction "2_2") (pintype "power_in"))
      (node (ref "R54.2") (pin "2") (pinfunction "2_2") (pintype "power_in"))
      (node (ref "U4.2") (pin "3") (pinfunction "M_3") (pintype "passive"))
    )
    (net (code "78") (name "Net-(U5.2-IN+)") (class "Default")
      (node (ref "R55.2") (pin "2") (pinfunction "2_2") (pintype "power_in"))
      (node (ref "U5.2") (pin "3") (pinfunction "IN+_3") (pintype "power_in"))
    )
    (net (code "79") (name "Net-(U5.2-IN-)") (class "Default")
      (node (ref "C3.2") (pin "1") (pinfunction "1_1") (pintype "power_in"))
      (node (ref "R29.2") (pin "2") (pinfunction "2_2") (pintype "power_in"))
      (node (ref "R41.2") (pin "1") (pinfunction "1_1") (pintype "power_in"))
      (node (ref "U5.2") (pin "2") (pinfunction "IN-_2") (pintype "power_in"))
    )
    (net (code "80") (name "Net-(U5.2-OUT)") (class "Default")
      (node (ref "C3.2") (pin "2") (pinfunction "2_2") (pintype "power_in"))
      (node (ref "P6.2") (pin "1") (pinfunction "1_1") (pintype "power_in"))
      (node (ref "R29.2") (pin "1") (pinfunction "1_1") (pintype "power_in"))
      (node (ref "R52.2") (pin "2") (pinfunction "2_2") (pintype "power_in"))
      (node (ref "U5.2") (pin "6") (pinfunction "OUT_6") (pintype "power_in"))
    )
    (net (code "81") (name "Net-(U6.2-IN+)") (class "Default")
      (node (ref "R53.2") (pin "1") (pinfunction "1_1") (pintype "power_in"))
      (node (ref "R56.2") (pin "2") (pinfunction "2_2") (pintype "power_in"))
      (node (ref "U6.2") (pin "3") (pinfunction "IN+_3") (pintype "power_in"))
    )
    (net (code "82") (name "Net-(U6.2-IN-)") (class "Default")
      (node (ref "C4.2") (pin "1") (pinfunction "1_1") (pintype "power_in"))
      (node (ref "R30.2") (pin "2") (pinfunction "2_2") (pintype "power_in"))
      (node (ref "R52.2") (pin "1") (pinfunction "1_1") (pintype "power_in"))
      (node (ref "U6.2") (pin "2") (pinfunction "IN-_2") (pintype "power_in"))
    )
    (net (code "83") (name "Net-(U7.2-HT+)") (class "Default")
      (node (ref "R68.2") (pin "1") (pinfunction "1_1") (pintype "power_in"))
      (node (ref "U7.2") (pin "1") (pinfunction "HT+_1") (pintype "passive"))
    )
    (net (code "84") (name "Net-(U7.2-M)") (class "Default")
      (node (ref "P9.2") (pin "1") (pinfunction "1_1") (pintype "power_in"))
      (node (ref "R69.2") (pin "2") (pinfunction "2_2") (pintype "power_in"))
      (node (ref "R82.2") (pin "2") (pinfunction "2_2") (pintype "power_in"))
      (node (ref "U7.2") (pin "3") (pinfunction "M_3") (pintype "passive"))
    )
    (net (code "85") (name "Net-(U8.2-IN+)") (class "Default")
      (node (ref "R83.2") (pin "2") (pinfunction "2_2") (pintype "power_in"))
      (node (ref "U8.2") (pin "3") (pinfunction "IN+_3") (pintype "power_in"))
    )
    (net (code "86") (name "Net-(U8.2-IN-)") (class "Default")
      (node (ref "C5.2") (pin "1") (pinfunction "1_1") (pintype "power_in"))
      (node (ref "R57.2") (pin "2") (pinfunction "2_2") (pintype "power_in"))
      (node (ref "R69.2") (pin "1") (pinfunction "1_1") (pintype "power_in"))
      (node (ref "U8.2") (pin "2") (pinfunction "IN-_2") (pintype "power_in"))
    )
    (net (code "87") (name "Net-(U8.2-OUT)") (class "Default")
      (node (ref "C5.2") (pin "2") (pinfunction "2_2") (pintype "power_in"))
      (node (ref "P10.2") (pin "1") (pinfunction "1_1") (pintype "power_in"))
      (node (ref "R57.2") (pin "1") (pinfunction "1_1") (pintype "power_in"))
      (node (ref "R80.2") (pin "2") (pinfunction "2_2") (pintype "power_in"))
      (node (ref "U8.2") (pin "6") (pinfunction "OUT_6") (pintype "power_in"))
    )
    (net (code "88") (name "Net-(U9.2-IN+)") (class "Default")
      (node (ref "R81.2") (pin "1") (pinfunction "1_1") (pintype "power_in"))
      (node (ref "R84.2") (pin "2") (pinfunction "2_2") (pintype "power_in"))
      (node (ref "U9.2") (pin "3") (pinfunction "IN+_3") (pintype "power_in"))
    )
    (net (code "89") (name "Net-(U9.2-IN-)") (class "Default")
      (node (ref "C6.2") (pin "1") (pinfunction "1_1") (pintype "power_in"))
      (node (ref "R58.2") (pin "2") (pinfunction "2_2") (pintype "power_in"))
      (node (ref "R80.2") (pin "1") (pinfunction "1_1") (pintype "power_in"))
      (node (ref "U9.2") (pin "2") (pinfunction "IN-_2") (pintype "power_in"))
    )
    (net (code "90") (name "unconnected-(U2.2-NC-Pad5)") (class "Default")
      (node (ref "U2.2") (pin "5") (pinfunction "NC_5") (pintype "passive+no_connect"))
    )
    (net (code "91") (name "unconnected-(U2.2-VOSTRIM-Pad1)") (class "Default")
      (node (ref "U2.2") (pin "1") (pinfunction "VOSTRIM_1") (pintype "passive+no_connect"))
    )
    (net (code "92") (name "unconnected-(U2.2-VOSTRIM-Pad8)") (class "Default")
      (node (ref "U2.2") (pin "8") (pinfunction "VOSTRIM_8") (pintype "passive+no_connect"))
    )
    (net (code "93") (name "unconnected-(U3.2-NC-Pad5)") (class "Default")
      (node (ref "U3.2") (pin "5") (pinfunction "NC_5") (pintype "passive+no_connect"))
    )
    (net (code "94") (name "unconnected-(U3.2-VOSTRIM-Pad1)") (class "Default")
      (node (ref "U3.2") (pin "1") (pinfunction "VOSTRIM_1") (pintype "passive+no_connect"))
    )
    (net (code "95") (name "unconnected-(U3.2-VOSTRIM-Pad8)") (class "Default")
      (node (ref "U3.2") (pin "8") (pinfunction "VOSTRIM_8") (pintype "passive+no_connect"))
    )
    (net (code "96") (name "unconnected-(U5.2-NC-Pad5)") (class "Default")
      (node (ref "U5.2") (pin "5") (pinfunction "NC_5") (pintype "passive+no_connect"))
    )
    (net (code "97") (name "unconnected-(U5.2-VOSTRIM-Pad1)") (class "Default")
      (node (ref "U5.2") (pin "1") (pinfunction "VOSTRIM_1") (pintype "passive+no_connect"))
    )
    (net (code "98") (name "unconnected-(U5.2-VOSTRIM-Pad8)") (class "Default")
      (node (ref "U5.2") (pin "8") (pinfunction "VOSTRIM_8") (pintype "passive+no_connect"))
    )
    (net (code "99") (name "unconnected-(U6.2-NC-Pad5)") (class "Default")
      (node (ref "U6.2") (pin "5") (pinfunction "NC_5") (pintype "passive+no_connect"))
    )
    (net (code "100") (name "unconnected-(U6.2-VOSTRIM-Pad1)") (class "Default")
      (node (ref "U6.2") (pin "1") (pinfunction "VOSTRIM_1") (pintype "passive+no_connect"))
    )
    (net (code "101") (name "unconnected-(U6.2-VOSTRIM-Pad8)") (class "Default")
      (node (ref "U6.2") (pin "8") (pinfunction "VOSTRIM_8") (pintype "passive+no_connect"))
    )
    (net (code "102") (name "unconnected-(U8.2-NC-Pad5)") (class "Default")
      (node (ref "U8.2") (pin "5") (pinfunction "NC_5") (pintype "passive+no_connect"))
    )
    (net (code "103") (name "unconnected-(U8.2-VOSTRIM-Pad1)") (class "Default")
      (node (ref "U8.2") (pin "1") (pinfunction "VOSTRIM_1") (pintype "passive+no_connect"))
    )
    (net (code "104") (name "unconnected-(U8.2-VOSTRIM-Pad8)") (class "Default")
      (node (ref "U8.2") (pin "8") (pinfunction "VOSTRIM_8") (pintype "passive+no_connect"))
    )
    (net (code "105") (name "unconnected-(U9.2-NC-Pad5)") (class "Default")
      (node (ref "U9.2") (pin "5") (pinfunction "NC_5") (pintype "passive+no_connect"))
    )
    (net (code "106") (name "unconnected-(U9.2-VOSTRIM-Pad1)") (class "Default")
      (node (ref "U9.2") (pin "1") (pinfunction "VOSTRIM_1") (pintype "passive+no_connect"))
    )
    (net (code "107") (name "unconnected-(U9.2-VOSTRIM-Pad8)") (class "Default")
      (node (ref "U9.2") (pin "8") (pinfunction "VOSTRIM_8") (pintype "passive+no_connect"))
    )
  )
)
